# 51-2001-01-13_04_Power_Module_Schematic.net
KiCad netlist of a schematic drawn in Altium Designer
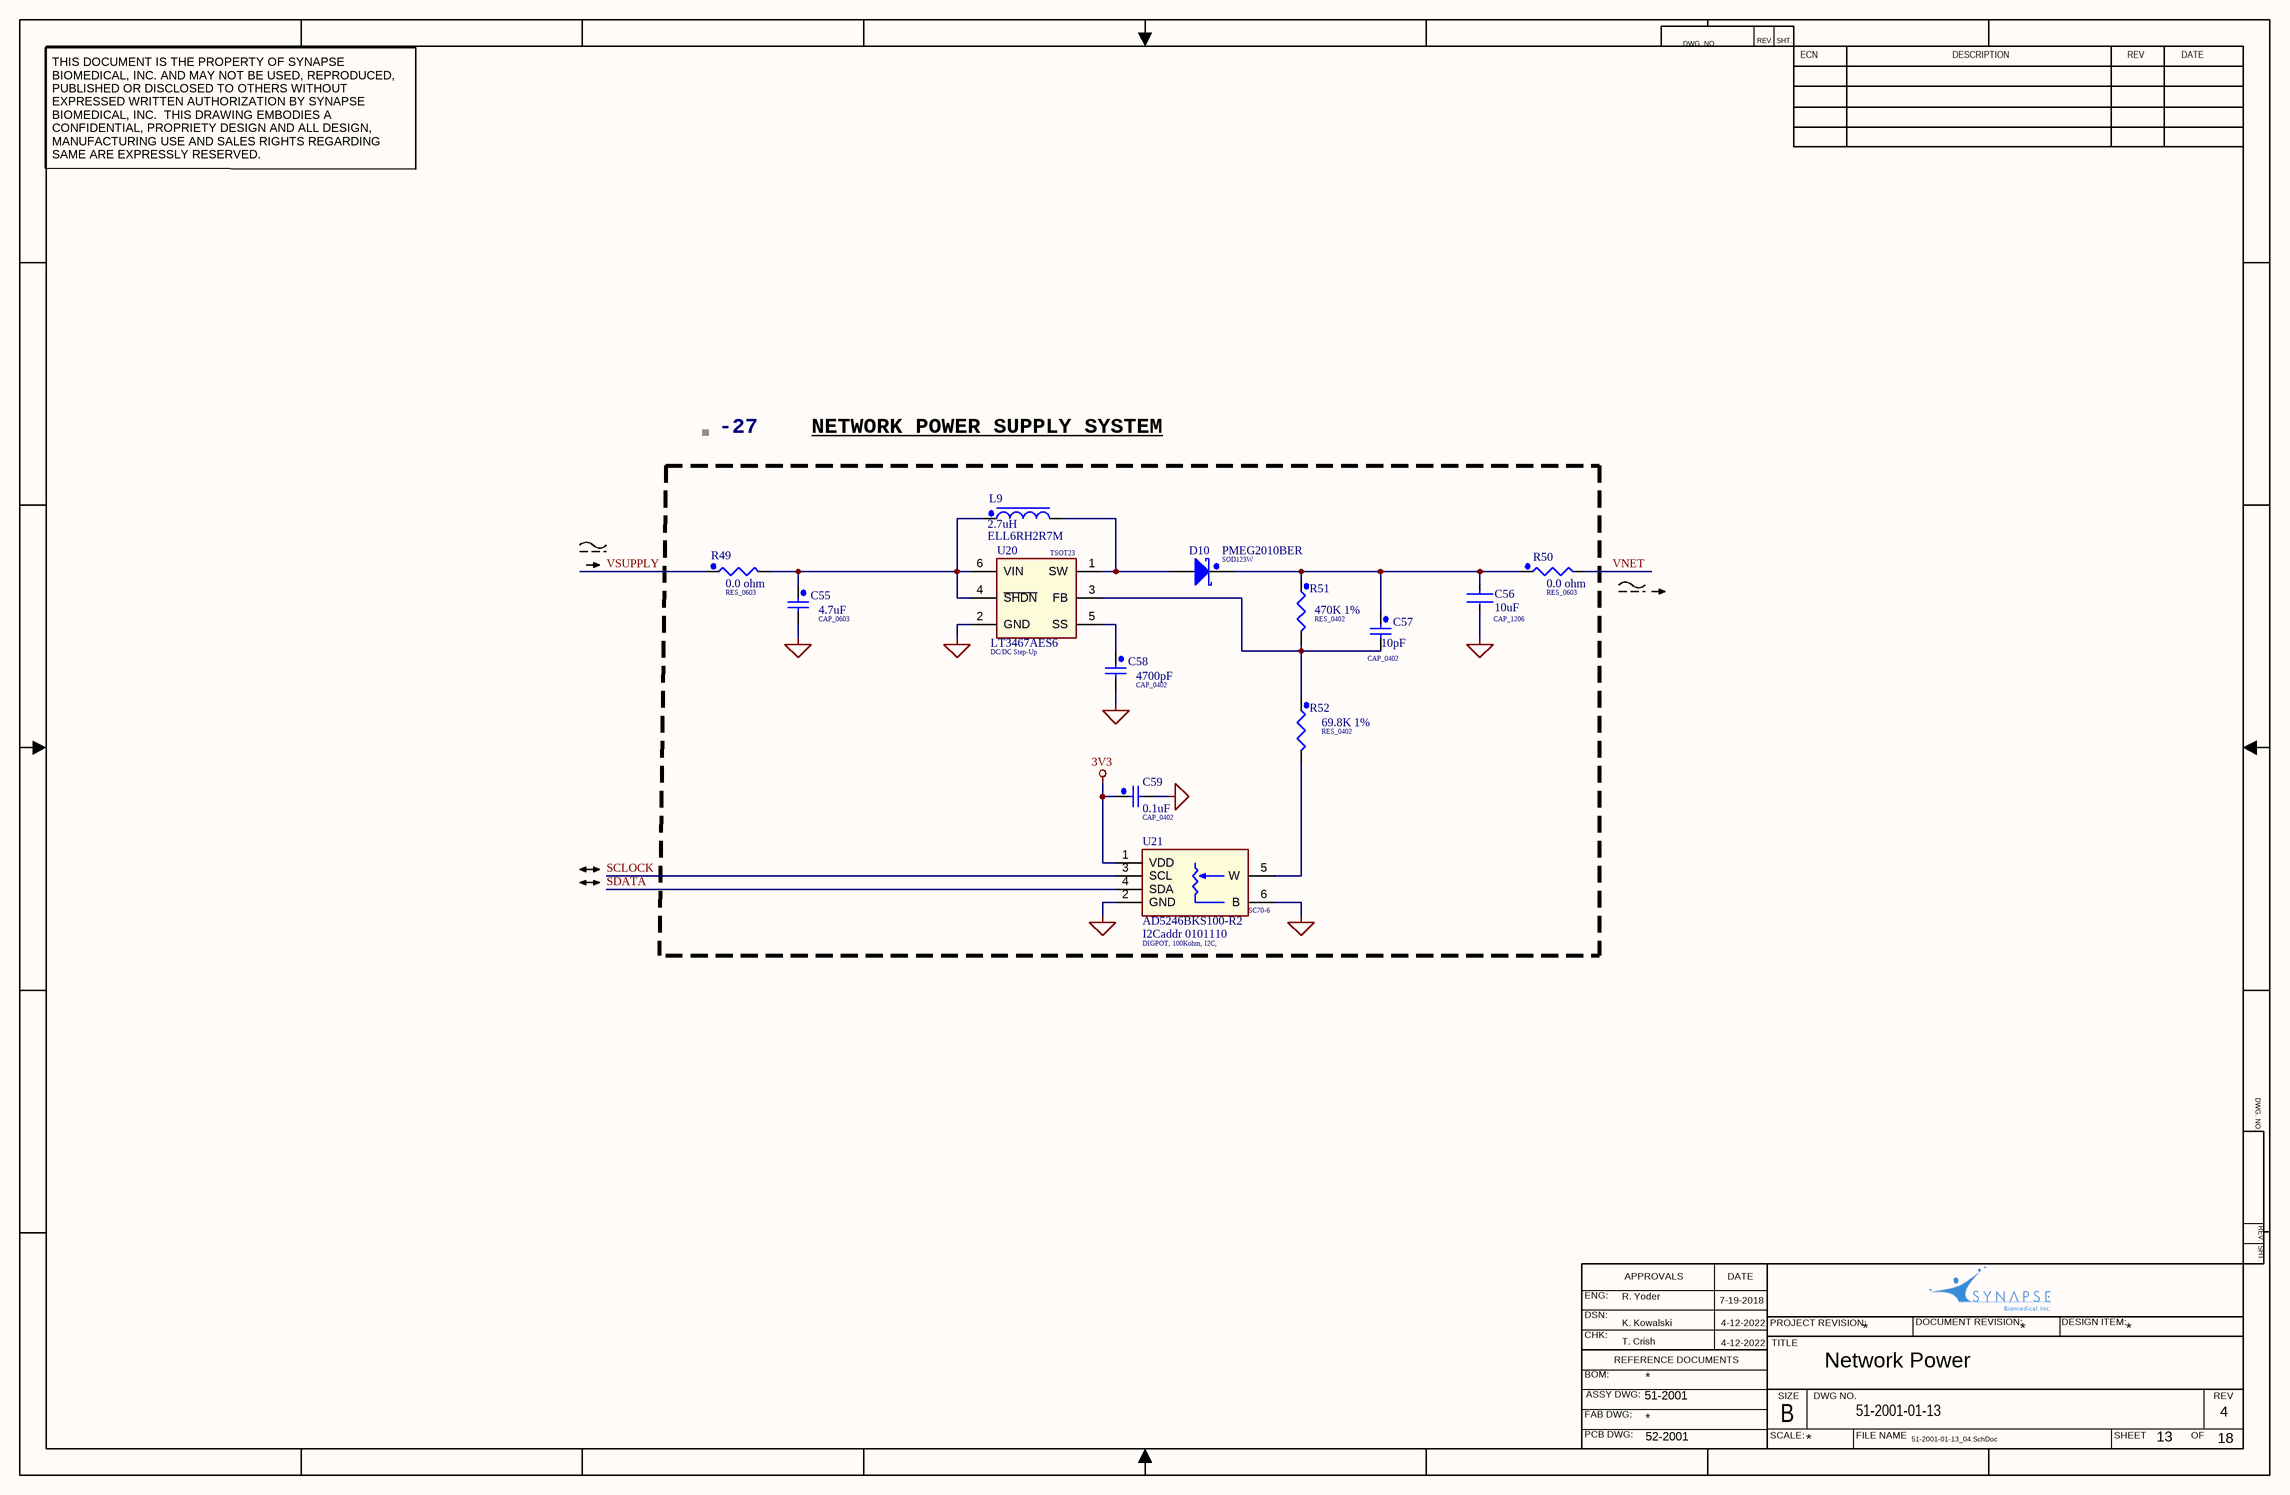
[diagram p0: 51-2001-01-13_04 Power Module Schematic.SchDoc]

(export (version "E")
  (design (tool "Eeschema 10.0.6"))
  (components
    (comp (ref "-27")
      (value "BOM_S1")
      (description "BOM item small graphic")
      (fields (field (name "XDESCRIPTION") "NETWORK POWER SUPPLY SYSTEM"))
      (libsource (lib "BOM_sym") (part "BOM_S1"))
    )
    (comp (ref "C55")
      (value "4.7uF")
      (footprint "CAP_0603")
      (description "4.7uF, 10V, X5R, 10%, 0603, RoHS")
      (fields
        (field (name "MFR") "Murata Electronics North America")
        (field (name "PACKAGEDESCRIPTION") "CAP_0603")
        (field (name "MPN") "GRM185R61A475KE11D")
      )
      (libsource (lib "NNPS Integrated Parts") (part "LMK107BJ475KA-T"))
    )
    (comp (ref "C56")
      (value "10uF")
      (footprint "FP-GRT31C-0_2-IPC_A")
      (description "Multi-Layer Ceramic Capacitor 10uF 50V X5R ±10% 1206 Emboss T/R\r\nGRT31CR61H106KE01L")
      (fields (field (name "TOLERANCE") "10%") (field (name "CASE/PACKAGE") "CAP_1206"))
      (libsource (lib "Altium Content Vault") (part "02cd4be3c70576c341d710602a673aa"))
    )
    (comp (ref "C57")
      (value "10pF")
      (footprint "CAP_0402")
      (description "10pF, 50V, C0G, 5%, 0402, RoHS")
      (fields
        (field (name "MFR") "Murata Electronics North America")
        (field (name "PACKAGEDESCRIPTION") "CAP_0402")
        (field (name "MPN") "GRM1555C1H100JA01D")
      )
      (libsource (lib "NNPS Integrated Parts") (part "GRM1555C1H100JZ01"))
    )
    (comp (ref "C58")
      (value "4700pF")
      (footprint "CAP_0402")
      (description "4.7uF, 50V,C0G, 0402, 10%, RoHS")
      (fields
        (field (name "MFR") "Murata Electronics North America")
        (field (name "PACKAGEDESCRIPTION") "CAP_0402")
        (field (name "MPN") "GRM155R71H472KA01D")
      )
      (libsource (lib "NNPS Integrated Parts") (part "C0402C472K5RACTU"))
    )
    (comp (ref "C59")
      (value "0.1uF")
      (footprint "CAP_0402")
      (description "0.1uF, 16V, X7R, 0402, RoHS")
      (fields
        (field (name "MFR") "Murata")
        (field (name "PACKAGEDESCRIPTION") "CAP_0402")
        (field (name "MPN") "GRM155R71C104KA88D")
      )
      (libsource (lib "NNPS Integrated Parts") (part "GRM155R71C104KA88D"))
    )
    (comp (ref "D10")
      (value "PMEG2010BER")
      (footprint "SOD123")
      (description "Schotty Diode, 20V, 1000mA, SOD123W, RoHS")
      (fields
        (field (name "MFR") "NXP")
        (field (name "PACKAGEDESCRIPTION") "SOD123W")
        (field (name "MPN") "PMEG2010BER,115")
      )
      (libsource (lib "NNPS Integrated Parts") (part "PMEG2010BER"))
    )
    (comp (ref "L9")
      (value "2.7uH")
      (footprint "IND-ELL-6RH")
      (description "2.7uH, 1.8A, 2626, 20%, RoHS")
      (fields
        (field (name "MFR") "Panasonic")
        (field (name "MPN") "ELL6RH2R7M")
        (field (name "Comment") "L_2u7_1A8_2626_20%")
      )
      (libsource (lib "NNPS Integrated Parts") (part "ELL6RH2R7M"))
    )
    (comp (ref "R49")
      (value "0.0 ohm")
      (footprint "RES_0603")
      (description "0.0 ohm, 1/16W, 0603, RoHS")
      (fields
        (field (name "MFR") "Vishay Dale")
        (field (name "PACKAGEDESCRIPTION") "RES_0603")
        (field (name "MPN") "CRCW06030000Z0EA")
      )
      (libsource (lib "NNPS Integrated Parts") (part "MCR03ERTJ000"))
    )
    (comp (ref "R50")
      (value "0.0 ohm")
      (footprint "RES_0603")
      (description "0.0 ohm, 1/16W, 0603, RoHS")
      (fields
        (field (name "MFR") "Vishay Dale")
        (field (name "PACKAGEDESCRIPTION") "RES_0603")
        (field (name "MPN") "CRCW06030000Z0EA")
      )
      (libsource (lib "NNPS Integrated Parts") (part "MCR03ERTJ000"))
    )
    (comp (ref "R51")
      (value "470K 1%")
      (footprint "RES_0402")
      (description "470K ohm, 1%, 1/16W, 0402,RoHS")
      (fields
        (field (name "MFR") "Vishay")
        (field (name "PACKAGEDESCRIPTION") "RES_0402")
        (field (name "MPN") "CRCW0402470KFKEDHP")
      )
      (libsource (lib "NNPS Integrated Parts") (part "CRCW0402374KFKED"))
    )
    (comp (ref "R52")
      (value "69.8K 1%")
      (footprint "RES_0402")
      (description "69.8K, 1%, 1/16W, 0402, RoHS")
      (fields
        (field (name "MFR") "Vishay")
        (field (name "PACKAGEDESCRIPTION") "RES_0402")
        (field (name "MPN") "CRCW040269K8FKTD")
      )
      (libsource (lib "NNPS Integrated Parts") (part "CRCW040243K2FKED"))
    )
    (comp (ref "U20")
      (value "DC/DC Step-Up")
      (footprint "SOT23-6")
      (description "DC, Booster, 2.4-16V, TSOT23")
      (fields
        (field (name "MFR") "Linear Technology")
        (field (name "PACKAGEDESCRIPTION") "TSOT23")
        (field (name "MPN") "LT3467AES6")
      )
      (libsource (lib "NNPS Integrated Parts") (part "LT3467AES6"))
    )
    (comp (ref "U21")
      (value "DIGPOT, 100Kohm, I2C,")
      (footprint "SC70-6")
      (description "DIGPOT, 100Kohm, I2C, SC70")
      (fields
        (field (name "MFR") "Analog Devices")
        (field (name "PACKAGEDESCRIPTION") "SC70-6")
        (field (name "NOTE") "I2Caddr 0101110")
        (field (name "MPN") "AD5246BKS100-R2")
      )
      (libsource (lib "NNPS Integrated Parts") (part "AD5246BKS100-R2"))
    )
  )
  (nets
    (net (code "1") (name "/SCLOCK") (class "Default")
      (node (ref "U21") (pin "3") (pinfunction "SCL_3") (pintype "passive"))
    )
    (net (code "2") (name "/SDATA") (class "Default")
      (node (ref "U21") (pin "4") (pinfunction "SDA_4") (pintype "passive"))
    )
    (net (code "3") (name "/VNET") (class "Default")
      (node (ref "R50") (pin "2") (pinfunction "2_2") (pintype "passive"))
    )
    (net (code "4") (name "/VSUPPLY") (class "Default")
      (node (ref "R49") (pin "1") (pinfunction "1_1") (pintype "passive"))
    )
    (net (code "5") (name "3V3") (class "Default")
      (node (ref "C59") (pin "1") (pinfunction "1_1") (pintype "passive"))
      (node (ref "U21") (pin "1") (pinfunction "VDD_1") (pintype "passive"))
    )
    (net (code "6") (name "GND") (class "Default")
      (node (ref "C55") (pin "2") (pinfunction "2_2") (pintype "passive"))
      (node (ref "C56") (pin "2") (pinfunction "2_2") (pintype "passive"))
      (node (ref "C58") (pin "2") (pinfunction "2_2") (pintype "passive"))
      (node (ref "C59") (pin "2") (pinfunction "2_2") (pintype "passive"))
      (node (ref "U20") (pin "2") (pinfunction "GND_2") (pintype "passive"))
      (node (ref "U21") (pin "2") (pinfunction "GND_2") (pintype "passive"))
      (node (ref "U21") (pin "6") (pinfunction "B_6") (pintype "passive"))
    )
    (net (code "7") (name "Net-(D10-A)") (class "Default")
      (node (ref "D10") (pin "2") (pinfunction "A_2") (pintype "passive"))
      (node (ref "L9") (pin "2") (pinfunction "2_2") (pintype "passive"))
      (node (ref "U20") (pin "1") (pinfunction "SW_1") (pintype "passive"))
    )
    (net (code "8") (name "Net-(D10-C)") (class "Default")
      (node (ref "C56") (pin "1") (pinfunction "1_1") (pintype "passive"))
      (node (ref "C57") (pin "1") (pinfunction "1_1") (pintype "passive"))
      (node (ref "D10") (pin "1") (pinfunction "C_1") (pintype "passive"))
      (node (ref "R50") (pin "1") (pinfunction "1_1") (pintype "passive"))
      (node (ref "R51") (pin "1") (pinfunction "1_1") (pintype "passive"))
    )
    (net (code "9") (name "Net-(U20-FB)") (class "Default")
      (node (ref "C57") (pin "2") (pinfunction "2_2") (pintype "passive"))
      (node (ref "R51") (pin "2") (pinfunction "2_2") (pintype "passive"))
      (node (ref "R52") (pin "1") (pinfunction "1_1") (pintype "passive"))
      (node (ref "U20") (pin "3") (pinfunction "FB_3") (pintype "passive"))
    )
    (net (code "10") (name "Net-(U20-SS)") (class "Default")
      (node (ref "C58") (pin "1") (pinfunction "1_1") (pintype "passive"))
      (node (ref "U20") (pin "5") (pinfunction "SS_5") (pintype "passive"))
    )
    (net (code "11") (name "Net-(U20-VIN)") (class "Default")
      (node (ref "C55") (pin "1") (pinfunction "1_1") (pintype "passive"))
      (node (ref "L9") (pin "1") (pinfunction "1_1") (pintype "passive"))
      (node (ref "R49") (pin "2") (pinfunction "2_2") (pintype "passive"))
      (node (ref "U20") (pin "4") (pinfunction "~{SHDN}_4") (pintype "passive"))
      (node (ref "U20") (pin "6") (pinfunction "VIN_6") (pintype "passive"))
    )
    (net (code "12") (name "Net-(U21-W)") (class "Default")
      (node (ref "R52") (pin "2") (pinfunction "2_2") (pintype "passive"))
      (node (ref "U21") (pin "5") (pinfunction "W_5") (pintype "passive"))
    )
  )
)
